# 01-POWER.net
KiCad netlist of a schematic drawn in Altium Designer
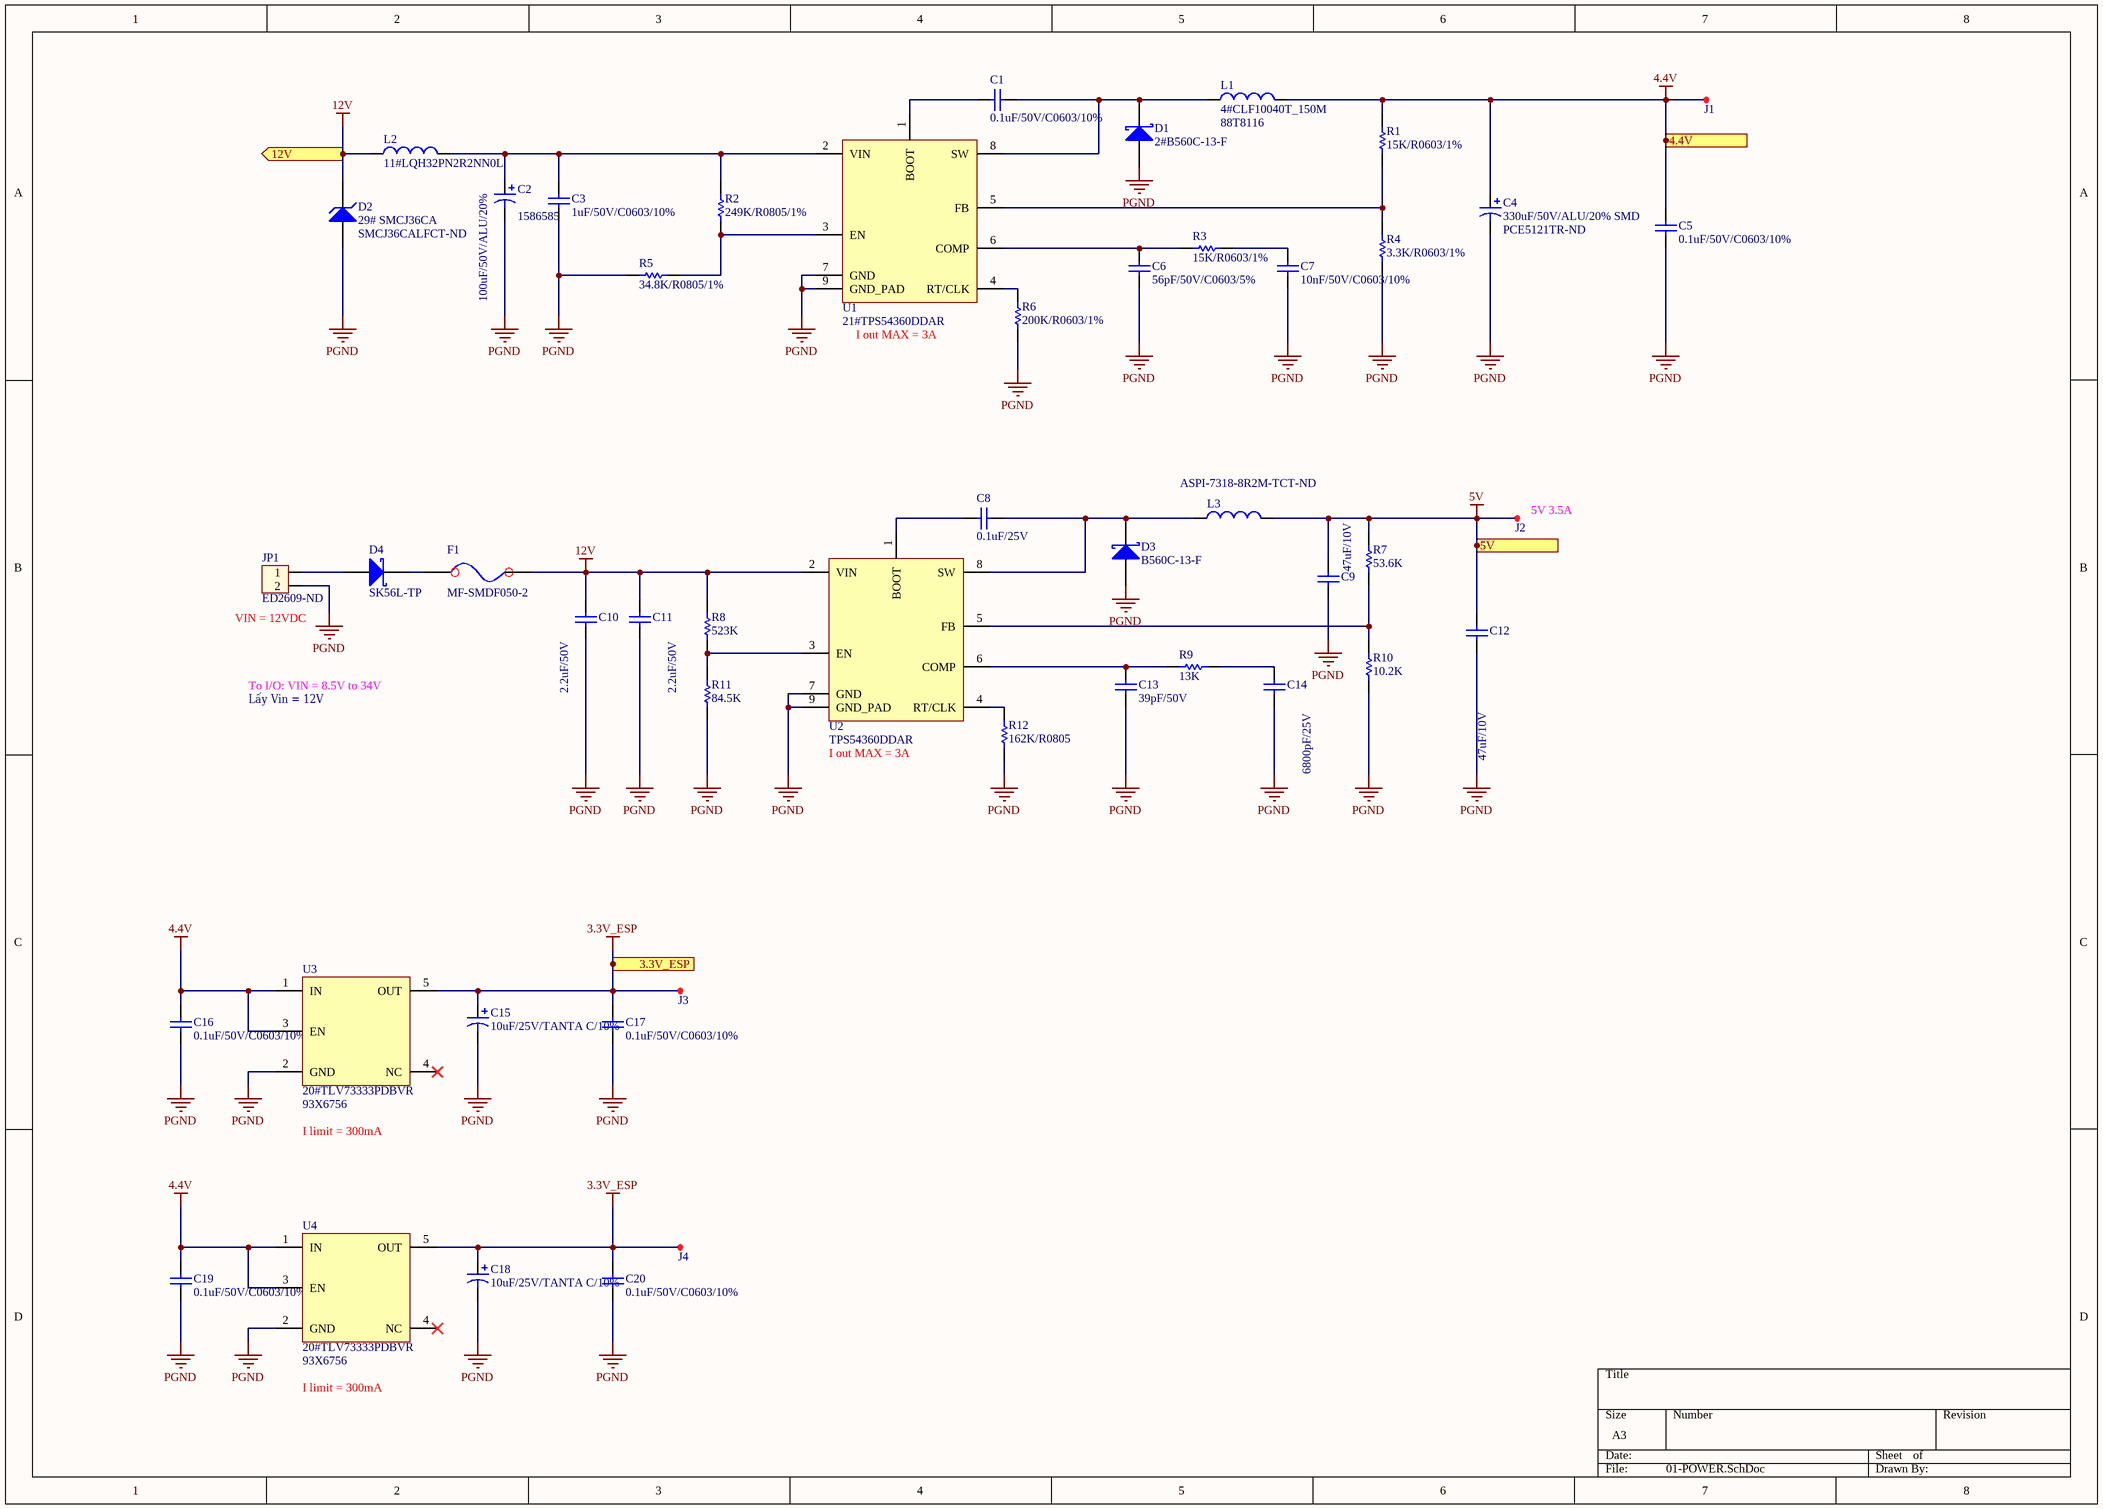
[diagram p0: 01-POWER.SchDoc]

(export (version "E")
  (design (tool "Eeschema 10.0.6"))
  (components
    (comp (ref "C1")
      (value "0.1uF/50V/C0603/10%")
      (footprint "Cap Ceramic 0603 SMD")
      (description "CAP CER 0.1UF 50V 10% X7R 0603")
      (fields
        (field (name "MANUFACTURER") "Murata Electronics North America")
        (field (name "MANUFACTURER PART NUMBER") "GRM188R71H104KA93D")
      )
      (libsource (lib "GSHT_181013") (part "0.1uF/50V/C0603/10%"))
    )
    (comp (ref "C2")
      (value "100uF/50V/ALU/20%")
      (footprint "CAP ALU CASE F SMD")
      (description "CAP ALU 100UF 20% 50V RADIAL")
      (fields
        (field (name "MANUFACTURER") "Panasonic Electronic Components")
        (field (name "MANUFACTURER PART NUMBER") "ECA-1HM101B")
        (field (name "SUPPLIER PART NUMBER 1") "1586585")
      )
      (libsource (lib "GSHT_181013") (part "100uF/50V/ALU 8X11.5/20%"))
    )
    (comp (ref "C3")
      (value "1uF/50V/C0603/10%")
      (footprint "Cap Ceramic 0603 SMD")
      (description "CAP CER 1UF 50V X7R 0603")
      (fields
        (field (name "MANUFACTURER") "Samsung Electro-Mechanics America, Inc.")
        (field (name "MANUFACTURER PART NUMBER") "CL21B105KBFNNNE")
      )
      (libsource (lib "GSHT_181013") (part "1uF/50V/C0603/10%"))
    )
    (comp (ref "C4")
      (value "330uF/50V/ALU/20% SMD")
      (footprint "CAP ALU CASE G SMD")
      (description "CAP ALU 330UF 20% 50V SMD")
      (fields
        (field (name "MANUFACTURER") "Nichicon")
        (field (name "MANUFACTURER PART NUMBER") "UPW1J331MHD")
        (field (name "SUPPLIER PART NUMBER 1") "PCE5121TR-ND")
      )
      (libsource (lib "GSHT_181013") (part "330uF/50V/ALU12.5X20mm/20%/7000Hrs"))
    )
    (comp (ref "C5")
      (value "0.1uF/50V/C0603/10%")
      (footprint "Cap Ceramic 0603 SMD")
      (description "CAP CER 0.1UF 50V 10% X7R 0603")
      (fields
        (field (name "MANUFACTURER") "Murata Electronics North America")
        (field (name "MANUFACTURER PART NUMBER") "GRM188R71H104KA93D")
      )
      (libsource (lib "GSHT_181013") (part "0.1uF/50V/C0603/10%"))
    )
    (comp (ref "C6")
      (value "56pF/50V/C0603/5%")
      (footprint "Cap Ceramic 0603 SMD")
      (description "Cap Ceramic 56pF 50V C0G 5% SMD 0603 125C Paper T/R")
      (fields
        (field (name "MANUFACTURER") "Samsung")
        (field (name "MANUFACTURER PART NUMBER") "CL10C560JB8NNNC")
      )
      (libsource (lib "GSHT_181013") (part "56pF/50V/C0603/5%"))
    )
    (comp (ref "C7")
      (value "10nF/50V/C0603/10%")
      (footprint "Cap Ceramic 0603 SMD")
      (description "CAP CER 10000PF 50V X7R 0603")
      (fields
        (field (name "MANUFACTURER") "Murata Electronics North America")
        (field (name "MANUFACTURER PART NUMBER") "GRM188R71H103KA01D")
      )
      (libsource (lib "GSHT_181013") (part "10nF/50V/C0603/10%"))
    )
    (comp (ref "C8")
      (value "0.1uF/25V")
      (footprint "CAP_CERA_C2012(CC0805INCH)")
      (description "0.1µF ±10% 25V Ceramic Capacitor X7R 0805 (2012 Metric)")
      (fields (field (name "MANUFACTURER") "AVX Corporation"))
      (libsource (lib "GSHT_181013") (part "0.1uF/50V/C0603/10%"))
    )
    (comp (ref "C9")
      (value "47uF/10V")
      (footprint "CAP_CERA_C2012(CC0805INCH)")
      (description "47µF ±20% 10V Ceramic Capacitor X5R 0805 (2012 Metric)")
      (fields (field (name "MANUFACTURER") "Murata"))
      (libsource (lib "GSHT_181013") (part "0.1uF/50V/C0603/10%"))
    )
    (comp (ref "C10")
      (value "2.2uF/50V")
      (footprint "CAP_CERA_C2012(CC0805INCH)")
      (description "2.2µF ±10% 50V Ceramic Capacitor JB 0805 (2012 Metric)")
      (fields (field (name "MANUFACTURER") "TDK"))
      (libsource (lib "GSHT_181013") (part "1uF/50V/C0603/10%"))
    )
    (comp (ref "C11")
      (value "2.2uF/50V")
      (footprint "CAP_CERA_C2012(CC0805INCH)")
      (description "2.2µF ±10% 50V Ceramic Capacitor JB 0805 (2012 Metric)")
      (fields (field (name "MANUFACTURER") "TDK"))
      (libsource (lib "GSHT_181013") (part "1uF/50V/C0603/10%"))
    )
    (comp (ref "C12")
      (value "47uF/10V")
      (footprint "CAP_CERA_C2012(CC0805INCH)")
      (description "47µF ±20% 10V Ceramic Capacitor X5R 0805 (2012 Metric)")
      (fields (field (name "MANUFACTURER") "Murata"))
      (libsource (lib "GSHT_181013") (part "0.1uF/50V/C0603/10%"))
    )
    (comp (ref "C13")
      (value "39pF/50V")
      (footprint "CAP_CERA_C2012(CC0805INCH)")
      (description "39pF ±10% 50V Ceramic Capacitor C0G, NP0 0805 (2012 Metric)")
      (fields (field (name "MANUFACTURER") "KEMET"))
      (libsource (lib "GSHT_181013") (part "56pF/50V/C0603/5%"))
    )
    (comp (ref "C14")
      (value "6800pF/25V")
      (footprint "CAP_CERA_C2012(CC0805INCH)")
      (description "6800pF ±10% 25V Ceramic Capacitor X7R 0805 (2012 Metric)")
      (fields (field (name "MANUFACTURER") "Wurth Electronics Inc."))
      (libsource (lib "GSHT_181013") (part "10nF/50V/C0603/10%"))
    )
    (comp (ref "C15")
      (value "10uF/25V/TANTA C/10%")
      (footprint "CAP TANT CASE C SMD")
      (description "Tantalum Capacitors - Solid SMD 25v 10uF 20%Tol Code C")
      (fields
        (field (name "MANUFACTURER") "Kyocera AVX")
        (field (name "MANUFACTURER PART NUMBER") "TAJB106M025RNJ")
      )
      (libsource (lib "GSHT_181013") (part "TAJB106M025RNJ"))
    )
    (comp (ref "C16")
      (value "0.1uF/50V/C0603/10%")
      (footprint "Cap Ceramic 0603 SMD")
      (description "CAP CER 0.1UF 50V 10% X7R 0603")
      (fields
        (field (name "MANUFACTURER") "Murata Electronics North America")
        (field (name "MANUFACTURER PART NUMBER") "GRM188R71H104KA93D")
      )
      (libsource (lib "GSHT_181013") (part "0.1uF/50V/C0603/10%"))
    )
    (comp (ref "C17")
      (value "0.1uF/50V/C0603/10%")
      (footprint "Cap Ceramic 0603 SMD")
      (description "CAP CER 0.1UF 50V 10% X7R 0603")
      (fields
        (field (name "MANUFACTURER") "Murata Electronics North America")
        (field (name "MANUFACTURER PART NUMBER") "GRM188R71H104KA93D")
      )
      (libsource (lib "GSHT_181013") (part "0.1uF/50V/C0603/10%"))
    )
    (comp (ref "C18")
      (value "10uF/25V/TANTA C/10%")
      (footprint "CAP TANT CASE C SMD")
      (description "Tantalum Capacitors - Solid SMD 25v 10uF 20%Tol Code C")
      (fields
        (field (name "MANUFACTURER") "Kyocera AVX")
        (field (name "MANUFACTURER PART NUMBER") "TAJB106M025RNJ")
      )
      (libsource (lib "GSHT_181013") (part "TAJB106M025RNJ"))
    )
    (comp (ref "C19")
      (value "0.1uF/50V/C0603/10%")
      (footprint "Cap Ceramic 0603 SMD")
      (description "CAP CER 0.1UF 50V 10% X7R 0603")
      (fields
        (field (name "MANUFACTURER") "Murata Electronics North America")
        (field (name "MANUFACTURER PART NUMBER") "GRM188R71H104KA93D")
      )
      (libsource (lib "GSHT_181013") (part "0.1uF/50V/C0603/10%"))
    )
    (comp (ref "C20")
      (value "0.1uF/50V/C0603/10%")
      (footprint "Cap Ceramic 0603 SMD")
      (description "CAP CER 0.1UF 50V 10% X7R 0603")
      (fields
        (field (name "MANUFACTURER") "Murata Electronics North America")
        (field (name "MANUFACTURER PART NUMBER") "GRM188R71H104KA93D")
      )
      (libsource (lib "GSHT_181013") (part "0.1uF/50V/C0603/10%"))
    )
    (comp (ref "D1")
      (value "2#B560C-13-F")
      (footprint "2# B560C")
      (description "DIODE SCHOTTKY 60V 5A SMC")
      (fields (field (name "MANUFACTURER") "Diodes") (field (name "MANUFACTURER PART NUMBER") "B560C-13-F"))
      (libsource (lib "GSHT_181013") (part "2#B560C-13-F"))
    )
    (comp (ref "D2")
      (value "29# SMCJ36CA")
      (footprint "29# diode SMCJ36A")
      (description "TVS DIODE 36VWM 58.1VC SMC")
      (fields
        (field (name "MANUFACTURER") "Littelfuse")
        (field (name "MANUFACTURER PART NUMBER") "SMCJ36CA")
        (field (name "SUPPLIER PART NUMBER 1") "SMCJ36CALFCT-ND")
      )
      (libsource (lib "GSHT_181013") (part "29# SMCJ36CA"))
    )
    (comp (ref "D3")
      (value "B560C-13-F")
      (footprint "2# B560C")
      (description "DIODE SCHOTTKY 60V 5A SMC")
      (libsource (lib "GSHT_181013") (part "2#B560C-13-F"))
    )
    (comp (ref "D4")
      (value "SK56L-TP")
      (footprint "30# SK56L-TPMSCT-ND")
      (description "DIODE SCHOTTKY 60V 5A DO214AB")
      (libsource (lib "GSHT_181013") (part "30# SK56L-TP"))
    )
    (comp (ref "F1")
      (value "MF-SMDF050-2")
      (footprint "13# MF-SMDF050")
      (description "PTC RESET FUSE 60V 550MA 2018")
      (libsource (lib "GSHT_181013") (part "13#MF-SMDF050-2"))
    )
    (comp (ref "J1")
      (value "TEST POINT")
      (footprint "TEST POINT 1mm")
      (description "TPoint")
      (libsource (lib "GSHT_181013") (part "PAD 1mm"))
    )
    (comp (ref "J2")
      (value "TEST POINT")
      (footprint "TEST POINT 1mm")
      (description "TPoint")
      (libsource (lib "GSHT_181013") (part "PAD 1mm"))
    )
    (comp (ref "J3")
      (value "TEST POINT")
      (footprint "TEST POINT 1mm")
      (description "TPoint")
      (libsource (lib "GSHT_181013") (part "PAD 1mm"))
    )
    (comp (ref "J4")
      (value "TEST POINT")
      (footprint "TEST POINT 1mm")
      (description "TPoint")
      (libsource (lib "GSHT_181013") (part "PAD 1mm"))
    )
    (comp (ref "JP1")
      (value "ED2609-ND")
      (footprint "DOMINO_OSTTC_2P")
      (description "2 Position Wire to Board Terminal Block Horizontal with Board 0.200\" (5.08mm) Through Hole")
      (libsource (lib "lpson") (part "Con2"))
    )
    (comp (ref "L1")
      (value "4#CLF10040T_150M")
      (footprint "4# clf10040XX")
      (description "FIXED IND 15uH 3.2A 40 MOHM (10.0×9.7×3.8)")
      (fields (field (name "SUPPLIER PART NUMBER 1") "88T8116"))
      (libsource (lib "GSHT_181013") (part "4#CLF10040T_150M"))
    )
    (comp (ref "L2")
      (value "11#LQH32PN2R2NN0L")
      (footprint "11# LQH32PN2R2")
      (description "Inductor Power Chip Shielded Wirewound 2.2uH 30% 1MHz Ferrite 1.6A 91.2mOhm DCR 1210 Embossed T/R")
      (fields
        (field (name "MANUFACTURER") "Murata")
        (field (name "MANUFACTURER PART NUMBER") "LQH32PN2R2NN0L")
      )
      (libsource (lib "GSHT_181013") (part "11#LQH32PN2R2NN0L"))
    )
    (comp (ref "L3")
      (value "ASPI-7318-8R2M-TCT-ND")
      (footprint "ASPI-7318-8R2M-TCT-ND")
      (description "8.2µH Shielded Wirewound Inductor 4A 68 mOhm Max Nonstandard")
      (libsource (lib "lpson") (part "Inductor"))
    )
    (comp (ref "R1")
      (value "15K/R0603/1%")
      (footprint "Res 0603 SMD")
      (description "RES SMD 15K OHM 1% 1/10W 0603")
      (fields
        (field (name "MANUFACTURER") "Yageo")
        (field (name "MANUFACTURER PART NUMBER") "RC0603FR-0715KL")
      )
      (libsource (lib "GSHT_181013") (part "15K/R0603/1%"))
    )
    (comp (ref "R2")
      (value "249K/R0805/1%")
      (footprint "Res 0805 SMD")
      (description "RES SMD 249K OHM 1% 1/10W 0805")
      (fields
        (field (name "MANUFACTURER") "Yageo")
        (field (name "MANUFACTURER PART NUMBER") "RC0603FR-07249KL")
      )
      (libsource (lib "GSHT_181013") (part "249K/R0805/1%"))
    )
    (comp (ref "R3")
      (value "15K/R0603/1%")
      (footprint "Res 0603 SMD")
      (description "RES SMD 15K OHM 1% 1/10W 0603")
      (fields
        (field (name "MANUFACTURER") "Yageo")
        (field (name "MANUFACTURER PART NUMBER") "RC0603FR-0715KL")
      )
      (libsource (lib "GSHT_181013") (part "15K/R0603/1%"))
    )
    (comp (ref "R4")
      (value "3.3K/R0603/1%")
      (footprint "Cap Ceramic 0603 SMD")
      (description "RES SMD 3.3K OHM 1% 1/10W 0603")
      (fields
        (field (name "MANUFACTURER") "Yageo")
        (field (name "MANUFACTURER PART NUMBER") "RC0603FR-073K3L")
      )
      (libsource (lib "GSHT_181013") (part "3.3K/R0603/1%"))
    )
    (comp (ref "R5")
      (value "34.8K/R0805/1%")
      (footprint "Res 0805 SMD")
      (description "Thick Film Resistors - SMD 34.8K OHM 1% 0805")
      (fields
        (field (name "MANUFACTURER") "Yageo")
        (field (name "MANUFACTURER PART NUMBER") "RC0603FR-0734K8L")
      )
      (libsource (lib "GSHT_181013") (part "34.8K/R0805/1%"))
    )
    (comp (ref "R6")
      (value "200K/R0603/1%")
      (footprint "Res 0603 SMD")
      (description "RES SMD 200K OHM 1% 1/10W 0603")
      (fields
        (field (name "MANUFACTURER") "Yageo")
        (field (name "MANUFACTURER PART NUMBER") "RC0603FR-07200KL")
      )
      (libsource (lib "GSHT_181013") (part "200K/R0603/1%"))
    )
    (comp (ref "R7")
      (value "53.6K")
      (footprint "Res 0805 SMD")
      (description "53.6 kOhms ±1% 0.125W, 1/8W Chip Resistor 0805 (2012 Metric) Automotive AEC-Q200 Thick Film")
      (libsource (lib "GSHT_181013") (part "15K/R0603/1%"))
    )
    (comp (ref "R8")
      (value "523K")
      (footprint "Res 0805 SMD")
      (description "523 kOhms ±1% 0.125W, 1/8W Chip Resistor 0805 (2012 Metric) Automotive AEC-Q200 Thick Film")
      (libsource (lib "GSHT_181013") (part "249K/R0805/1%"))
    )
    (comp (ref "R9")
      (value "13K")
      (footprint "Res 0805 SMD")
      (description "13 kOhms ±1% 0.125W, 1/8W Chip Resistor 0805 (2012 Metric) Automotive AEC-Q200 Thick Film")
      (libsource (lib "GSHT_181013") (part "15K/R0603/1%"))
    )
    (comp (ref "R10")
      (value "10.2K")
      (footprint "Res 0805 SMD")
      (description "10.2 kOhms ±1% 0.125W, 1/8W Chip Resistor 0805 (2012 Metric) Automotive AEC-Q200 Thick Film")
      (libsource (lib "GSHT_181013") (part "3.3K/R0603/1%"))
    )
    (comp (ref "R11")
      (value "84.5K")
      (footprint "Res 0805 SMD")
      (description "84.5 kOhms ±1% 0.125W, 1/8W Chip Resistor 0805 (2012 Metric) Automotive AEC-Q200 Thick Film")
      (libsource (lib "GSHT_181013") (part "34.8K/R0805/1%"))
    )
    (comp (ref "R12")
      (value "162K/R0805")
      (footprint "Res 0805 SMD")
      (description "162 kOhms ±1% 0.125W, 1/8W Chip Resistor 0805 (2012 Metric) Automotive AEC-Q200 Thick Film")
      (libsource (lib "GSHT_181013") (part "200K/R0603/1%"))
    )
    (comp (ref "U1")
      (value "21#TPS54360DDAR")
      (footprint "21# TPS54360")
      (description "Voltage Regulators - Switching Regulators 60 Vin,3.5 A,SD DC-DC Converter")
      (fields
        (field (name "MANUFACTURER") "Texas Instruments")
        (field (name "MANUFACTURER PART NUMBER") "TPS54360DDAR")
      )
      (libsource (lib "GSHT_181013") (part "21#TPS54360DDAR"))
    )
    (comp (ref "U2")
      (value "TPS54360DDAR")
      (footprint "21# TPS54360")
      (libsource (lib "GSHT_181013") (part "21#TPS54360DDAR"))
    )
    (comp (ref "U3")
      (value "20#TLV73333PDBVR")
      (footprint "TLV73333PDBVR - SOT23-65")
      (description "LDO Regulator Pos 3.3V 0.3A 5-Pin SOT-23 T/R")
      (fields
        (field (name "MANUFACTURER") "Texas Instruments")
        (field (name "MANUFACTURER PART NUMBER") "TLV73333PDBVR")
        (field (name "SUPPLIER PART NUMBER 1") "93X6756")
      )
      (libsource (lib "GSHT_181013") (part "20#TLV73333PDBVR"))
    )
    (comp (ref "U4")
      (value "20#TLV73333PDBVR")
      (footprint "TLV73333PDBVR - SOT23-65")
      (description "LDO Regulator Pos 3.3V 0.3A 5-Pin SOT-23 T/R")
      (fields
        (field (name "MANUFACTURER") "Texas Instruments")
        (field (name "MANUFACTURER PART NUMBER") "TLV73333PDBVR")
        (field (name "SUPPLIER PART NUMBER 1") "93X6756")
      )
      (libsource (lib "GSHT_181013") (part "20#TLV73333PDBVR"))
    )
  )
  (nets
    (net (code "1") (name "3.3V_ESP") (class "Default")
      (node (ref "C15") (pin "1") (pinfunction "1_1") (pintype "passive"))
      (node (ref "C17") (pin "2") (pinfunction "2_2") (pintype "passive"))
      (node (ref "C18") (pin "1") (pinfunction "1_1") (pintype "passive"))
      (node (ref "C20") (pin "2") (pinfunction "2_2") (pintype "passive"))
      (node (ref "J3") (pin "1") (pinfunction "TP_1") (pintype "passive"))
      (node (ref "J4") (pin "1") (pinfunction "TP_1") (pintype "passive"))
      (node (ref "U3") (pin "5") (pinfunction "OUT_5") (pintype "passive"))
      (node (ref "U4") (pin "5") (pinfunction "OUT_5") (pintype "passive"))
    )
    (net (code "2") (name "4.4V") (class "Default")
      (node (ref "C16") (pin "2") (pinfunction "2_2") (pintype "passive"))
      (node (ref "C19") (pin "2") (pinfunction "2_2") (pintype "passive"))
      (node (ref "C4") (pin "1") (pinfunction "1_1") (pintype "passive"))
      (node (ref "C5") (pin "2") (pinfunction "2_2") (pintype "passive"))
      (node (ref "J1") (pin "1") (pinfunction "TP_1") (pintype "passive"))
      (node (ref "L1") (pin "2") (pinfunction "2_2") (pintype "passive"))
      (node (ref "R1") (pin "2") (pinfunction "2_2") (pintype "passive"))
      (node (ref "U3") (pin "1") (pinfunction "IN_1") (pintype "passive"))
      (node (ref "U3") (pin "3") (pinfunction "EN_3") (pintype "passive"))
      (node (ref "U4") (pin "1") (pinfunction "IN_1") (pintype "passive"))
      (node (ref "U4") (pin "3") (pinfunction "EN_3") (pintype "passive"))
    )
    (net (code "3") (name "5V") (class "Default")
      (node (ref "C12") (pin "2") (pinfunction "2_2") (pintype "passive"))
      (node (ref "C9") (pin "2") (pinfunction "2_2") (pintype "passive"))
      (node (ref "J2") (pin "1") (pinfunction "TP_1") (pintype "passive"))
      (node (ref "L3") (pin "2") (pinfunction "2_2") (pintype "passive"))
      (node (ref "R7") (pin "2") (pinfunction "2_2") (pintype "passive"))
    )
    (net (code "4") (name "12V") (class "Default")
      (node (ref "C10") (pin "2") (pinfunction "2_2") (pintype "passive"))
      (node (ref "C11") (pin "2") (pinfunction "2_2") (pintype "passive"))
      (node (ref "D2") (pin "2") (pinfunction "K_2") (pintype "passive"))
      (node (ref "F1") (pin "2") (pinfunction "OUT_2") (pintype "passive"))
      (node (ref "L2") (pin "1") (pinfunction "1_1") (pintype "passive"))
      (node (ref "R8") (pin "2") (pinfunction "2_2") (pintype "passive"))
      (node (ref "U2") (pin "2") (pinfunction "VIN_2") (pintype "passive"))
    )
    (net (code "5") (name "Net-(C7-Pad2)") (class "Default")
      (node (ref "C7") (pin "2") (pinfunction "2_2") (pintype "passive"))
      (node (ref "R3") (pin "1") (pinfunction "1_1") (pintype "passive"))
    )
    (net (code "6") (name "Net-(C14-Pad2)") (class "Default")
      (node (ref "C14") (pin "2") (pinfunction "2_2") (pintype "passive"))
      (node (ref "R9") (pin "1") (pinfunction "1_1") (pintype "passive"))
    )
    (net (code "7") (name "Net-(D1-K)") (class "Default")
      (node (ref "C1") (pin "2") (pinfunction "2_2") (pintype "passive"))
      (node (ref "D1") (pin "2") (pinfunction "K_2") (pintype "passive"))
      (node (ref "L1") (pin "1") (pinfunction "1_1") (pintype "passive"))
      (node (ref "U1") (pin "8") (pinfunction "SW_8") (pintype "passive"))
    )
    (net (code "8") (name "Net-(D3-K)") (class "Default")
      (node (ref "C8") (pin "1") (pinfunction "1_1") (pintype "passive"))
      (node (ref "D3") (pin "2") (pinfunction "K_2") (pintype "passive"))
      (node (ref "L3") (pin "1") (pinfunction "1_1") (pintype "passive"))
      (node (ref "U2") (pin "8") (pinfunction "SW_8") (pintype "passive"))
    )
    (net (code "9") (name "Net-(D4-A)") (class "Default")
      (node (ref "D4") (pin "1") (pinfunction "A_1") (pintype "passive"))
      (node (ref "JP1") (pin "1") (pinfunction "1_1") (pintype "passive"))
    )
    (net (code "10") (name "Net-(D4-K)") (class "Default")
      (node (ref "D4") (pin "2") (pinfunction "K_2") (pintype "passive"))
      (node (ref "F1") (pin "1") (pinfunction "IN_1") (pintype "passive"))
    )
    (net (code "11") (name "Net-(U1-BOOT)") (class "Default")
      (node (ref "C1") (pin "1") (pinfunction "1_1") (pintype "passive"))
      (node (ref "U1") (pin "1") (pinfunction "BOOT_1") (pintype "passive"))
    )
    (net (code "12") (name "Net-(U1-COMP)") (class "Default")
      (node (ref "C6") (pin "2") (pinfunction "2_2") (pintype "passive"))
      (node (ref "R3") (pin "2") (pinfunction "2_2") (pintype "passive"))
      (node (ref "U1") (pin "6") (pinfunction "COMP_6") (pintype "passive"))
    )
    (net (code "13") (name "Net-(U1-EN)") (class "Default")
      (node (ref "R2") (pin "1") (pinfunction "1_1") (pintype "passive"))
      (node (ref "R5") (pin "2") (pinfunction "2_2") (pintype "passive"))
      (node (ref "U1") (pin "3") (pinfunction "EN_3") (pintype "passive"))
    )
    (net (code "14") (name "Net-(U1-FB)") (class "Default")
      (node (ref "R1") (pin "1") (pinfunction "1_1") (pintype "passive"))
      (node (ref "R4") (pin "2") (pinfunction "2_2") (pintype "passive"))
      (node (ref "U1") (pin "5") (pinfunction "FB_5") (pintype "passive"))
    )
    (net (code "15") (name "Net-(U1-RT{slash}CLK)") (class "Default")
      (node (ref "R6") (pin "1") (pinfunction "1_1") (pintype "passive"))
      (node (ref "U1") (pin "4") (pinfunction "RT/CLK_4") (pintype "passive"))
    )
    (net (code "16") (name "Net-(U1-VIN)") (class "Default")
      (node (ref "C2") (pin "1") (pinfunction "1_1") (pintype "passive"))
      (node (ref "C3") (pin "2") (pinfunction "2_2") (pintype "passive"))
      (node (ref "L2") (pin "2") (pinfunction "2_2") (pintype "passive"))
      (node (ref "R2") (pin "2") (pinfunction "2_2") (pintype "passive"))
      (node (ref "U1") (pin "2") (pinfunction "VIN_2") (pintype "passive"))
    )
    (net (code "17") (name "Net-(U2-BOOT)") (class "Default")
      (node (ref "C8") (pin "2") (pinfunction "2_2") (pintype "passive"))
      (node (ref "U2") (pin "1") (pinfunction "BOOT_1") (pintype "passive"))
    )
    (net (code "18") (name "Net-(U2-COMP)") (class "Default")
      (node (ref "C13") (pin "2") (pinfunction "2_2") (pintype "passive"))
      (node (ref "R9") (pin "2") (pinfunction "2_2") (pintype "passive"))
      (node (ref "U2") (pin "6") (pinfunction "COMP_6") (pintype "passive"))
    )
    (net (code "19") (name "Net-(U2-EN)") (class "Default")
      (node (ref "R11") (pin "2") (pinfunction "2_2") (pintype "passive"))
      (node (ref "R8") (pin "1") (pinfunction "1_1") (pintype "passive"))
      (node (ref "U2") (pin "3") (pinfunction "EN_3") (pintype "passive"))
    )
    (net (code "20") (name "Net-(U2-FB)") (class "Default")
      (node (ref "R10") (pin "2") (pinfunction "2_2") (pintype "passive"))
      (node (ref "R7") (pin "1") (pinfunction "1_1") (pintype "passive"))
      (node (ref "U2") (pin "5") (pinfunction "FB_5") (pintype "passive"))
    )
    (net (code "21") (name "Net-(U2-RT{slash}CLK)") (class "Default")
      (node (ref "R12") (pin "1") (pinfunction "1_1") (pintype "passive"))
      (node (ref "U2") (pin "4") (pinfunction "RT/CLK_4") (pintype "passive"))
    )
    (net (code "22") (name "PGND") (class "Default")
      (node (ref "C10") (pin "1") (pinfunction "1_1") (pintype "passive"))
      (node (ref "C11") (pin "1") (pinfunction "1_1") (pintype "passive"))
      (node (ref "C12") (pin "1") (pinfunction "1_1") (pintype "passive"))
      (node (ref "C13") (pin "1") (pinfunction "1_1") (pintype "passive"))
      (node (ref "C14") (pin "1") (pinfunction "1_1") (pintype "passive"))
      (node (ref "C15") (pin "2") (pinfunction "2_2") (pintype "passive"))
      (node (ref "C16") (pin "1") (pinfunction "1_1") (pintype "passive"))
      (node (ref "C17") (pin "1") (pinfunction "1_1") (pintype "passive"))
      (node (ref "C18") (pin "2") (pinfunction "2_2") (pintype "passive"))
      (node (ref "C19") (pin "1") (pinfunction "1_1") (pintype "passive"))
      (node (ref "C2") (pin "2") (pinfunction "2_2") (pintype "passive"))
      (node (ref "C20") (pin "1") (pinfunction "1_1") (pintype "passive"))
      (node (ref "C3") (pin "1") (pinfunction "1_1") (pintype "passive"))
      (node (ref "C4") (pin "2") (pinfunction "2_2") (pintype "passive"))
      (node (ref "C5") (pin "1") (pinfunction "1_1") (pintype "passive"))
      (node (ref "C6") (pin "1") (pinfunction "1_1") (pintype "passive"))
      (node (ref "C7") (pin "1") (pinfunction "1_1") (pintype "passive"))
      (node (ref "C9") (pin "1") (pinfunction "1_1") (pintype "passive"))
      (node (ref "D1") (pin "1") (pinfunction "A_1") (pintype "passive"))
      (node (ref "D2") (pin "1") (pinfunction "A_1") (pintype "passive"))
      (node (ref "D3") (pin "1") (pinfunction "A_1") (pintype "passive"))
      (node (ref "JP1") (pin "2") (pinfunction "2_2") (pintype "passive"))
      (node (ref "R10") (pin "1") (pinfunction "1_1") (pintype "passive"))
      (node (ref "R11") (pin "1") (pinfunction "1_1") (pintype "passive"))
      (node (ref "R12") (pin "2") (pinfunction "2_2") (pintype "passive"))
      (node (ref "R4") (pin "1") (pinfunction "1_1") (pintype "passive"))
      (node (ref "R5") (pin "1") (pinfunction "1_1") (pintype "passive"))
      (node (ref "R6") (pin "2") (pinfunction "2_2") (pintype "passive"))
      (node (ref "U1") (pin "7") (pinfunction "GND_7") (pintype "passive"))
      (node (ref "U1") (pin "9") (pinfunction "GND_PAD_9") (pintype "passive"))
      (node (ref "U2") (pin "7") (pinfunction "GND_7") (pintype "passive"))
      (node (ref "U2") (pin "9") (pinfunction "GND_PAD_9") (pintype "passive"))
      (node (ref "U3") (pin "2") (pinfunction "GND_2") (pintype "passive"))
      (node (ref "U4") (pin "2") (pinfunction "GND_2") (pintype "passive"))
    )
    (net (code "23") (name "unconnected-(U3-NC-Pad4)") (class "Default")
      (node (ref "U3") (pin "4") (pinfunction "NC_4") (pintype "passive+no_connect"))
    )
    (net (code "24") (name "unconnected-(U4-NC-Pad4)") (class "Default")
      (node (ref "U4") (pin "4") (pinfunction "NC_4") (pintype "passive+no_connect"))
    )
  )
)
